# Sensor_Glove_Pheripherals-X01.net
KiCad netlist of a schematic drawn in Altium Designer
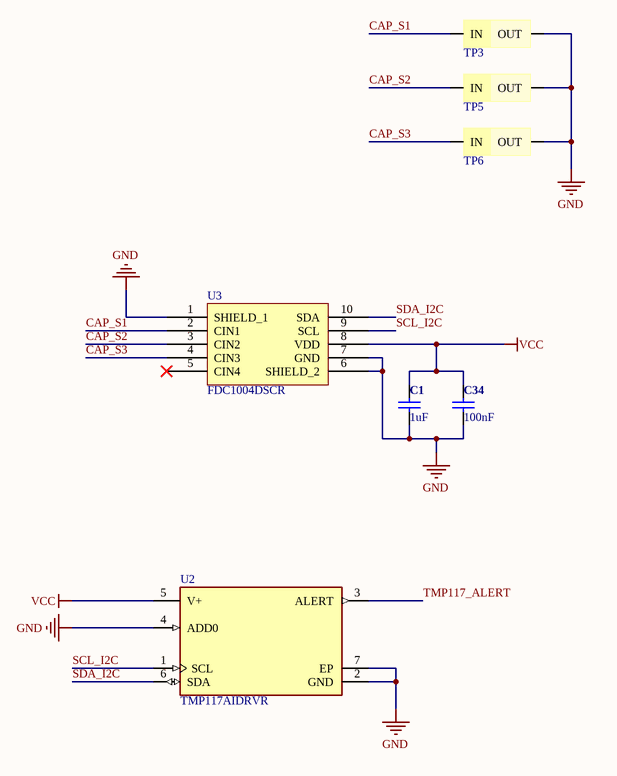
[diagram p0: Sensor_Glove_Pheripherals-X01.SchDoc]

(export (version "E")
  (design (tool "Eeschema 10.0.6"))
  (components
    (comp (ref "C1")
      (value "1uF")
      (footprint "C0402")
      (fields
        (field (name "MANUFACTURER") "Yageo")
        (field (name "MANUFACTURER PART NUMBER") "CC0402MRX5R5BB105")
        (field (name "TOLERANCE") "20%")
      )
      (libsource (lib "DB-X02") (part "C-0402(1005)"))
    )
    (comp (ref "C34")
      (value "100nF")
      (footprint "C0402")
      (fields
        (field (name "MANUFACTURER") "Taiyo Yuden")
        (field (name "MANUFACTURER PART NUMBER") "TMK105BJ104KV-F")
        (field (name "TOLERANCE") "10%")
      )
      (libsource (lib "DB-X02") (part "C-0402(1005)"))
    )
    (comp (ref "TP3")
      (value "JUMPER")
      (footprint "JUMPER")
      (description "SHUNT LP W/HANDLE 2 POS 30AU")
      (fields
        (field (name "MANUFACTURER") "TE Connectivity")
        (field (name "MANUFACTURER PART NUMBER") "8815452")
      )
      (libsource (lib "DB-X02") (part "JUMPER"))
    )
    (comp (ref "TP5")
      (value "JUMPER")
      (footprint "JUMPER")
      (description "SHUNT LP W/HANDLE 2 POS 30AU")
      (fields
        (field (name "MANUFACTURER") "TE Connectivity")
        (field (name "MANUFACTURER PART NUMBER") "8815452")
      )
      (libsource (lib "DB-X02") (part "JUMPER"))
    )
    (comp (ref "TP6")
      (value "JUMPER")
      (footprint "JUMPER")
      (description "SHUNT LP W/HANDLE 2 POS 30AU")
      (fields
        (field (name "MANUFACTURER") "TE Connectivity")
        (field (name "MANUFACTURER PART NUMBER") "8815452")
      )
      (libsource (lib "DB-X02") (part "JUMPER"))
    )
    (comp (ref "U2")
      (value "TMP117AIDRVR")
      (footprint "TMP117AIDRVR")
      (description "TEMPERATURE SENSOR")
      (fields
        (field (name "OCTOPART") "https://octopart.com/tmp117aidrvr-texas+instruments-95511044")
        (field (name "MANUFACTURER") "Texas Instruments")
      )
      (libsource (lib "DB-X01") (part "bceab6869a9cb85cf5675529ee35ce4"))
    )
    (comp (ref "U3")
      (value "4 CHANNEL CDC")
      (footprint "WSON-10 3X3MM")
      (description "Analog Circuit, 1 Func, 4 Channel, PDSO10")
      (fields
        (field (name "MANUFACTURER") "Texas Instruments")
        (field (name "MANUFACTURER PART NUMBER") "FDC1004DSCR")
      )
      (libsource (lib "DB-X02") (part "FDC1004"))
    )
  )
  (nets
    (net (code "1") (name "/CAP_S1") (class "Default")
      (node (ref "TP3") (pin "1") (pinfunction "IN_1") (pintype "passive"))
      (node (ref "U3") (pin "2") (pinfunction "CIN1_2") (pintype "passive"))
    )
    (net (code "2") (name "/CAP_S2") (class "Default")
      (node (ref "TP5") (pin "1") (pinfunction "IN_1") (pintype "passive"))
      (node (ref "U3") (pin "3") (pinfunction "CIN2_3") (pintype "passive"))
    )
    (net (code "3") (name "/CAP_S3") (class "Default")
      (node (ref "TP6") (pin "1") (pinfunction "IN_1") (pintype "passive"))
      (node (ref "U3") (pin "4") (pinfunction "CIN3_4") (pintype "passive"))
    )
    (net (code "4") (name "/SCL_I2C") (class "Default")
      (node (ref "U2") (pin "1") (pinfunction "SCL_1") (pintype "input"))
      (node (ref "U3") (pin "9") (pinfunction "SCL_9") (pintype "passive"))
    )
    (net (code "5") (name "/SDA_I2C") (class "Default")
      (node (ref "U2") (pin "6") (pinfunction "SDA_6") (pintype "bidirectional"))
      (node (ref "U3") (pin "10") (pinfunction "SDA_10") (pintype "passive"))
    )
    (net (code "6") (name "/TMP117_ALERT") (class "Default")
      (node (ref "U2") (pin "3") (pinfunction "ALERT_3") (pintype "output"))
    )
    (net (code "7") (name "GND") (class "Default")
      (node (ref "C1") (pin "2") (pinfunction "2_2") (pintype "passive"))
      (node (ref "C34") (pin "2") (pinfunction "2_2") (pintype "passive"))
      (node (ref "TP3") (pin "2") (pinfunction "OUT_2") (pintype "passive"))
      (node (ref "TP5") (pin "2") (pinfunction "OUT_2") (pintype "passive"))
      (node (ref "TP6") (pin "2") (pinfunction "OUT_2") (pintype "passive"))
      (node (ref "U2") (pin "2") (pinfunction "GND_2") (pintype "power_in"))
      (node (ref "U2") (pin "4") (pinfunction "ADD0_4") (pintype "input"))
      (node (ref "U2") (pin "7") (pinfunction "EP_7") (pintype "passive"))
      (node (ref "U3") (pin "1") (pinfunction "SHIELD_1_1") (pintype "passive"))
      (node (ref "U3") (pin "6") (pinfunction "SHIELD_2_6") (pintype "passive"))
      (node (ref "U3") (pin "7") (pinfunction "GND_7") (pintype "passive"))
    )
    (net (code "8") (name "VCC") (class "Default")
      (node (ref "C1") (pin "1") (pinfunction "1_1") (pintype "passive"))
      (node (ref "C34") (pin "1") (pinfunction "1_1") (pintype "passive"))
      (node (ref "U2") (pin "5") (pinfunction "V+_5") (pintype "power_in"))
      (node (ref "U3") (pin "8") (pinfunction "VDD_8") (pintype "passive"))
    )
    (net (code "9") (name "unconnected-(U3-CIN4-Pad5)") (class "Default")
      (node (ref "U3") (pin "5") (pinfunction "CIN4_5") (pintype "passive+no_connect"))
    )
  )
)
